# V2.net
KiCad netlist of a schematic drawn in Altium Designer
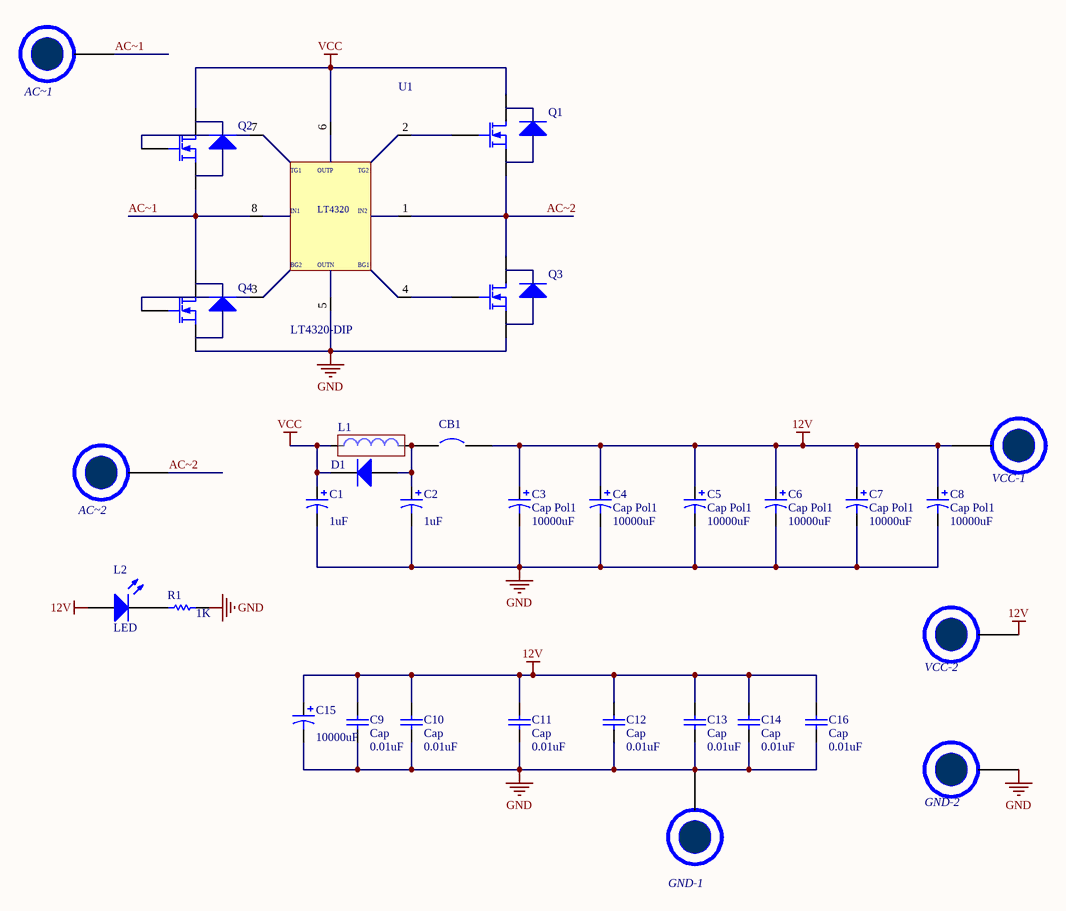
[diagram p0: 节能组取电V2.SchDoc]

(export (version "E")
  (design (tool "Eeschema 10.0.6"))
  (components
    (comp (ref "AC~1") (value "PIN") (footprint "PIN") (libsource (lib "常用元件库") (part "PIN")))
    (comp (ref "AC~2") (value "PIN") (footprint "PIN") (libsource (lib "常用元件库") (part "PIN")))
    (comp (ref "C1")
      (value "1uF")
      (footprint "C2012")
      (description "Polarized Capacitor (Radial)")
      (fields (field (name "Comment") "Cap Pol1") (field (name "PUBLISHER") "Altium Limited"))
      (libsource (lib "Miscellaneous Devices") (part "Cap Pol1"))
    )
    (comp (ref "C2")
      (value "1uF")
      (footprint "C2012")
      (description "Polarized Capacitor (Radial)")
      (fields (field (name "Comment") "Cap Pol1") (field (name "PUBLISHER") "Altium Limited"))
      (libsource (lib "Miscellaneous Devices") (part "Cap Pol1"))
    )
    (comp (ref "C3")
      (value "Cap Pol1")
      (footprint "RB7.6-15")
      (description "Polarized Capacitor (Radial)")
      (fields (field (name "ALTIUM_VALUE") "10000uF") (field (name "PUBLISHER") "Altium Limited"))
      (libsource (lib "Miscellaneous Devices") (part "Cap Pol1"))
    )
    (comp (ref "C4")
      (value "Cap Pol1")
      (footprint "RB7.6-15")
      (description "Polarized Capacitor (Radial)")
      (fields (field (name "ALTIUM_VALUE") "10000uF") (field (name "PUBLISHER") "Altium Limited"))
      (libsource (lib "Miscellaneous Devices") (part "Cap Pol1"))
    )
    (comp (ref "C5")
      (value "Cap Pol1")
      (footprint "RB7.6-15")
      (description "Polarized Capacitor (Radial)")
      (fields (field (name "ALTIUM_VALUE") "10000uF") (field (name "PUBLISHER") "Altium Limited"))
      (libsource (lib "Miscellaneous Devices") (part "Cap Pol1"))
    )
    (comp (ref "C6")
      (value "Cap Pol1")
      (footprint "RB7.6-15")
      (description "Polarized Capacitor (Radial)")
      (fields (field (name "ALTIUM_VALUE") "10000uF") (field (name "PUBLISHER") "Altium Limited"))
      (libsource (lib "Miscellaneous Devices") (part "Cap Pol1"))
    )
    (comp (ref "C7")
      (value "Cap Pol1")
      (footprint "RB7.6-15")
      (description "Polarized Capacitor (Radial)")
      (fields (field (name "ALTIUM_VALUE") "10000uF") (field (name "PUBLISHER") "Altium Limited"))
      (libsource (lib "Miscellaneous Devices") (part "Cap Pol1"))
    )
    (comp (ref "C8")
      (value "Cap Pol1")
      (footprint "RB7.6-15")
      (description "Polarized Capacitor (Radial)")
      (fields (field (name "ALTIUM_VALUE") "10000uF") (field (name "PUBLISHER") "Altium Limited"))
      (libsource (lib "Miscellaneous Devices") (part "Cap Pol1"))
    )
    (comp (ref "C9")
      (value "Cap")
      (footprint "C2012")
      (description "Capacitor")
      (fields (field (name "ALTIUM_VALUE") "0.01uF") (field (name "PUBLISHER") "Altium Limited"))
      (libsource (lib "Miscellaneous Devices") (part "Cap"))
    )
    (comp (ref "C10")
      (value "Cap")
      (footprint "C2012")
      (description "Capacitor")
      (fields (field (name "ALTIUM_VALUE") "0.01uF") (field (name "PUBLISHER") "Altium Limited"))
      (libsource (lib "Miscellaneous Devices") (part "Cap"))
    )
    (comp (ref "C11")
      (value "Cap")
      (footprint "C2012")
      (description "Capacitor")
      (fields (field (name "ALTIUM_VALUE") "0.01uF") (field (name "PUBLISHER") "Altium Limited"))
      (libsource (lib "Miscellaneous Devices") (part "Cap"))
    )
    (comp (ref "C12")
      (value "Cap")
      (footprint "C2012")
      (description "Capacitor")
      (fields (field (name "ALTIUM_VALUE") "0.01uF") (field (name "PUBLISHER") "Altium Limited"))
      (libsource (lib "Miscellaneous Devices") (part "Cap"))
    )
    (comp (ref "C13")
      (value "Cap")
      (footprint "C2012")
      (description "Capacitor")
      (fields (field (name "ALTIUM_VALUE") "0.01uF") (field (name "PUBLISHER") "Altium Limited"))
      (libsource (lib "Miscellaneous Devices") (part "Cap"))
    )
    (comp (ref "C14")
      (value "Cap")
      (footprint "C2012")
      (description "Capacitor")
      (fields (field (name "ALTIUM_VALUE") "0.01uF") (field (name "PUBLISHER") "Altium Limited"))
      (libsource (lib "Miscellaneous Devices") (part "Cap"))
    )
    (comp (ref "C15")
      (value "10000uF")
      (footprint "RB7.6-15")
      (description "Polarized Capacitor (Radial)")
      (fields (field (name "Comment") "Cap Pol1") (field (name "PUBLISHER") "Altium Limited"))
      (libsource (lib "Miscellaneous Devices") (part "Cap Pol1"))
    )
    (comp (ref "C16")
      (value "Cap")
      (footprint "C2012")
      (description "Capacitor")
      (fields (field (name "ALTIUM_VALUE") "0.01uF") (field (name "PUBLISHER") "Altium Limited"))
      (libsource (lib "Miscellaneous Devices") (part "Cap"))
    )
    (comp (ref "CB1")
      (value "Circuit Breaker")
      (footprint "SPST-2")
      (fields (field (name "PUBLISHER") "Altium Limited"))
      (libsource (lib "Miscellaneous Devices") (part "Circuit Breaker"))
    )
    (comp (ref "D1")
      (value "Diode 1N4001")
      (footprint "SK54")
      (description "1 Amp General Purpose Rectifier")
      (fields (field (name "PUBLISHER") "Altium Limited"))
      (libsource (lib "Miscellaneous Devices") (part "Diode 1N4001"))
    )
    (comp (ref "GND-1") (value "PIN") (footprint "PIN") (libsource (lib "常用元件库") (part "PIN")))
    (comp (ref "GND-2") (value "PIN") (footprint "PIN") (libsource (lib "常用元件库") (part "PIN")))
    (comp (ref "L1")
      (value "33uH")
      (footprint "SMD-EC-F16")
      (description "Inductor")
      (libsource (lib "Landzo") (part "Inductor"))
    )
    (comp (ref "L2") (value "LED") (footprint "C2012") (libsource (lib "Sparks") (part "LED")))
    (comp (ref "Q1")
      (value "MOSFET-N")
      (footprint "mos")
      (description "N-Channel MOSFET")
      (fields (field (name "PUBLISHER") "Altium Limited"))
      (libsource (lib "原理图") (part "MOSFET-N"))
    )
    (comp (ref "Q2")
      (value "MOSFET-N")
      (footprint "mos")
      (description "N-Channel MOSFET")
      (fields (field (name "PUBLISHER") "Altium Limited"))
      (libsource (lib "原理图") (part "MOSFET-N"))
    )
    (comp (ref "Q3")
      (value "MOSFET-N")
      (footprint "mos")
      (description "N-Channel MOSFET")
      (fields (field (name "PUBLISHER") "Altium Limited"))
      (libsource (lib "原理图") (part "MOSFET-N"))
    )
    (comp (ref "Q4")
      (value "MOSFET-N")
      (footprint "mos")
      (description "N-Channel MOSFET")
      (fields (field (name "PUBLISHER") "Altium Limited"))
      (libsource (lib "原理图") (part "MOSFET-N"))
    )
    (comp (ref "R1")
      (value "1K")
      (footprint "R2012")
      (description "贴片电阻")
      (fields (field (name "Comment") "Res") (field (name "PUBLISHER") "Altium Limited"))
      (libsource (lib "Sparks") (part "Res"))
    )
    (comp (ref "U1") (value "LT4320-DIP") (footprint "DIP-8") (libsource (lib "2号库") (part "LT4320-DIP")))
    (comp (ref "VCC-1") (value "PIN") (footprint "PIN") (libsource (lib "常用元件库") (part "PIN")))
    (comp (ref "VCC-2") (value "PIN") (footprint "PIN") (libsource (lib "常用元件库") (part "PIN")))
  )
  (nets
    (net (code "1") (name "/AC~1") (class "Default")
      (node (ref "AC~1") (pin "1") (pinfunction "PIN_1") (pintype "passive"))
      (node (ref "Q2") (pin "3") (pinfunction "S_3") (pintype "passive"))
      (node (ref "Q4") (pin "2") (pinfunction "D_2") (pintype "passive"))
      (node (ref "U1") (pin "8") (pinfunction "8_8") (pintype "passive"))
    )
    (net (code "2") (name "/AC~2") (class "Default")
      (node (ref "AC~2") (pin "1") (pinfunction "PIN_1") (pintype "passive"))
      (node (ref "Q1") (pin "3") (pinfunction "S_3") (pintype "passive"))
      (node (ref "Q3") (pin "2") (pinfunction "D_2") (pintype "passive"))
      (node (ref "U1") (pin "1") (pinfunction "1_1") (pintype "passive"))
    )
    (net (code "3") (name "12V") (class "Default")
      (node (ref "C10") (pin "2") (pinfunction "2_2") (pintype "passive"))
      (node (ref "C11") (pin "2") (pinfunction "2_2") (pintype "passive"))
      (node (ref "C12") (pin "2") (pinfunction "2_2") (pintype "passive"))
      (node (ref "C13") (pin "2") (pinfunction "2_2") (pintype "passive"))
      (node (ref "C14") (pin "2") (pinfunction "2_2") (pintype "passive"))
      (node (ref "C15") (pin "1") (pinfunction "1_1") (pintype "passive"))
      (node (ref "C16") (pin "2") (pinfunction "2_2") (pintype "passive"))
      (node (ref "C3") (pin "1") (pinfunction "1_1") (pintype "passive"))
      (node (ref "C4") (pin "1") (pinfunction "1_1") (pintype "passive"))
      (node (ref "C5") (pin "1") (pinfunction "1_1") (pintype "passive"))
      (node (ref "C6") (pin "1") (pinfunction "1_1") (pintype "passive"))
      (node (ref "C7") (pin "1") (pinfunction "1_1") (pintype "passive"))
      (node (ref "C8") (pin "1") (pinfunction "1_1") (pintype "passive"))
      (node (ref "C9") (pin "2") (pinfunction "2_2") (pintype "passive"))
      (node (ref "CB1") (pin "2") (pinfunction "2_2") (pintype "passive"))
      (node (ref "L2") (pin "1") (pinfunction "A_1") (pintype "passive"))
      (node (ref "VCC-1") (pin "1") (pinfunction "PIN_1") (pintype "passive"))
      (node (ref "VCC-2") (pin "1") (pinfunction "PIN_1") (pintype "passive"))
    )
    (net (code "4") (name "GND") (class "Default")
      (node (ref "C1") (pin "2") (pinfunction "2_2") (pintype "passive"))
      (node (ref "C10") (pin "1") (pinfunction "1_1") (pintype "passive"))
      (node (ref "C11") (pin "1") (pinfunction "1_1") (pintype "passive"))
      (node (ref "C12") (pin "1") (pinfunction "1_1") (pintype "passive"))
      (node (ref "C13") (pin "1") (pinfunction "1_1") (pintype "passive"))
      (node (ref "C14") (pin "1") (pinfunction "1_1") (pintype "passive"))
      (node (ref "C15") (pin "2") (pinfunction "2_2") (pintype "passive"))
      (node (ref "C16") (pin "1") (pinfunction "1_1") (pintype "passive"))
      (node (ref "C2") (pin "2") (pinfunction "2_2") (pintype "passive"))
      (node (ref "C3") (pin "2") (pinfunction "2_2") (pintype "passive"))
      (node (ref "C4") (pin "2") (pinfunction "2_2") (pintype "passive"))
      (node (ref "C5") (pin "2") (pinfunction "2_2") (pintype "passive"))
      (node (ref "C6") (pin "2") (pinfunction "2_2") (pintype "passive"))
      (node (ref "C7") (pin "2") (pinfunction "2_2") (pintype "passive"))
      (node (ref "C8") (pin "2") (pinfunction "2_2") (pintype "passive"))
      (node (ref "C9") (pin "1") (pinfunction "1_1") (pintype "passive"))
      (node (ref "GND-1") (pin "1") (pinfunction "PIN_1") (pintype "passive"))
      (node (ref "GND-2") (pin "1") (pinfunction "PIN_1") (pintype "passive"))
      (node (ref "Q3") (pin "3") (pinfunction "S_3") (pintype "passive"))
      (node (ref "Q4") (pin "3") (pinfunction "S_3") (pintype "passive"))
      (node (ref "R1") (pin "2") (pinfunction "2_2") (pintype "passive"))
      (node (ref "U1") (pin "5") (pinfunction "5_5") (pintype "passive"))
    )
    (net (code "5") (name "Net-(D1-A)") (class "Default")
      (node (ref "C2") (pin "1") (pinfunction "1_1") (pintype "passive"))
      (node (ref "CB1") (pin "1") (pinfunction "1_1") (pintype "passive"))
      (node (ref "D1") (pin "1") (pinfunction "A_1") (pintype "passive"))
      (node (ref "L1") (pin "2") (pinfunction "2_2") (pintype "passive"))
    )
    (net (code "6") (name "Net-(L2-K)") (class "Default")
      (node (ref "L2") (pin "2") (pinfunction "K_2") (pintype "passive"))
      (node (ref "R1") (pin "1") (pinfunction "1_1") (pintype "passive"))
    )
    (net (code "7") (name "Net-(Q1-G)") (class "Default")
      (node (ref "Q1") (pin "1") (pinfunction "G_1") (pintype "passive"))
      (node (ref "U1") (pin "2") (pinfunction "2_2") (pintype "passive"))
    )
    (net (code "8") (name "Net-(Q2-G)") (class "Default")
      (node (ref "Q2") (pin "1") (pinfunction "G_1") (pintype "passive"))
      (node (ref "U1") (pin "7") (pinfunction "7_7") (pintype "passive"))
    )
    (net (code "9") (name "Net-(Q3-G)") (class "Default")
      (node (ref "Q3") (pin "1") (pinfunction "G_1") (pintype "passive"))
      (node (ref "U1") (pin "4") (pinfunction "4_4") (pintype "passive"))
    )
    (net (code "10") (name "Net-(Q4-G)") (class "Default")
      (node (ref "Q4") (pin "1") (pinfunction "G_1") (pintype "passive"))
      (node (ref "U1") (pin "3") (pinfunction "3_3") (pintype "passive"))
    )
    (net (code "11") (name "VCC") (class "Default")
      (node (ref "C1") (pin "1") (pinfunction "1_1") (pintype "passive"))
      (node (ref "D1") (pin "2") (pinfunction "K_2") (pintype "passive"))
      (node (ref "L1") (pin "1") (pinfunction "1_1") (pintype "passive"))
      (node (ref "Q1") (pin "2") (pinfunction "D_2") (pintype "passive"))
      (node (ref "Q2") (pin "2") (pinfunction "D_2") (pintype "passive"))
      (node (ref "U1") (pin "6") (pinfunction "6_6") (pintype "passive"))
    )
  )
)
